# SL_Config_2E.net
KiCad netlist of a schematic drawn in Altium Designer
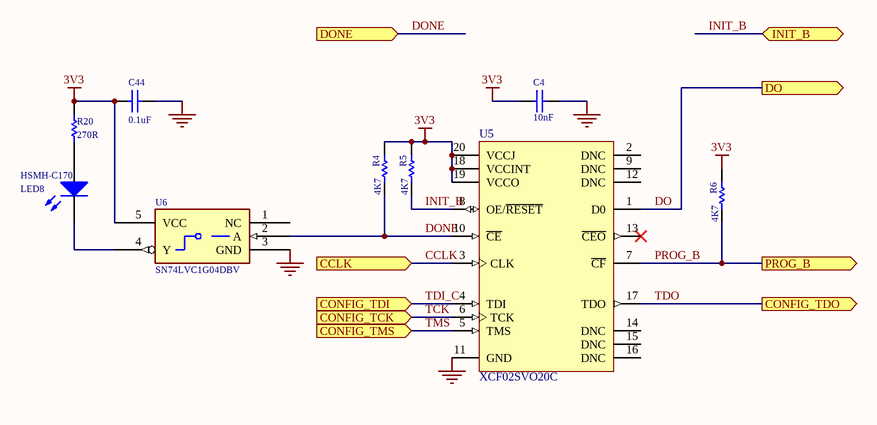
[diagram p0: SL_Config_2E.SchDoc]

(export (version "E")
  (design (tool "Eeschema 10.0.6"))
  (components
    (comp (ref "C4")
      (value "10nF")
      (footprint "CC1608-0603")
      (description "Capacitor")
      (libsource (lib "SpiritLevel_2E") (part "CAP"))
    )
    (comp (ref "C44")
      (value "0.1uF")
      (footprint "CC2012-0805")
      (description "Capacitor")
      (libsource (lib "SpiritLevel_2E") (part "CAP"))
    )
    (comp (ref "LED8")
      (value "HSMH-C170")
      (footprint "Spirit_Level_Project:SMD _LED")
      (description "Typical RED GaAs SMD LED Agilent make")
      (libsource (lib "SpiritLevel_2E") (part "HSMX-C670"))
    )
    (comp (ref "R4")
      (value "4K7")
      (footprint "Spirit_Level_Project:CR2012-0805")
      (description "Resistor")
      (libsource (lib "SpiritLevel_2E") (part "RES"))
    )
    (comp (ref "R5")
      (value "4K7")
      (footprint "Spirit_Level_Project:CR2012-0805")
      (description "Resistor")
      (libsource (lib "SpiritLevel_2E") (part "RES"))
    )
    (comp (ref "R6")
      (value "4K7")
      (footprint "Spirit_Level_Project:CR2012-0805")
      (description "Resistor")
      (libsource (lib "SpiritLevel_2E") (part "RES"))
    )
    (comp (ref "R20")
      (value "270R")
      (footprint "Spirit_Level_Project:CR2012-0805")
      (description "Resistor")
      (libsource (lib "SpiritLevel_2E") (part "RES"))
    )
    (comp (ref "U5")
      (value "XCF02SVO20C")
      (footprint "Spirit_Level_Project:VO20")
      (libsource (lib "SpiritLevel_2E") (part "XCF02SVO20C"))
    )
    (comp (ref "U6")
      (value "SN74LVC1G04DBV")
      (footprint "Spirit_Level_Project:SO-G5/P.95")
      (fields (field (name "MANUFACTURER") "TI"))
      (libsource (lib "SpiritLevel_2E") (part "SN74AHC1G04DBVR"))
    )
  )
  (nets
    (net (code "1") (name "/CCLK") (class "Default")
      (node (ref "U5") (pin "3") (pinfunction "CLK_3") (pintype "input"))
    )
    (net (code "2") (name "/DO") (class "Default")
      (node (ref "U5") (pin "1") (pinfunction "D0_1") (pintype "tri_state"))
    )
    (net (code "3") (name "/DONE") (class "Default")
      (node (ref "R4") (pin "2") (pinfunction "2_2") (pintype "passive"))
      (node (ref "U5") (pin "10") (pinfunction "~{CE}_10") (pintype "input"))
      (node (ref "U6") (pin "2") (pinfunction "A_2") (pintype "input"))
    )
    (net (code "4") (name "/INIT_B") (class "Default")
      (node (ref "R5") (pin "2") (pinfunction "2_2") (pintype "passive"))
      (node (ref "U5") (pin "8") (pinfunction "OE/~{RESET}_8") (pintype "bidirectional"))
    )
    (net (code "5") (name "/PROG_B") (class "Default")
      (node (ref "R6") (pin "2") (pinfunction "2_2") (pintype "passive"))
      (node (ref "U5") (pin "7") (pinfunction "~{CF}_7") (pintype "open_collector"))
    )
    (net (code "6") (name "/TCK") (class "Default")
      (node (ref "U5") (pin "6") (pinfunction "TCK_6") (pintype "input"))
    )
    (net (code "7") (name "/TDI_C") (class "Default")
      (node (ref "U5") (pin "4") (pinfunction "TDI_4") (pintype "input"))
    )
    (net (code "8") (name "/TDO") (class "Default")
      (node (ref "U5") (pin "17") (pinfunction "TDO_17") (pintype "output"))
    )
    (net (code "9") (name "/TMS") (class "Default")
      (node (ref "U5") (pin "5") (pinfunction "TMS_5") (pintype "input"))
    )
    (net (code "10") (name "3V3") (class "Default")
      (node (ref "C4") (pin "1") (pinfunction "1_1") (pintype "passive"))
      (node (ref "C44") (pin "2") (pinfunction "2_2") (pintype "passive"))
      (node (ref "R20") (pin "2") (pinfunction "2_2") (pintype "passive"))
      (node (ref "R4") (pin "1") (pinfunction "1_1") (pintype "passive"))
      (node (ref "R5") (pin "1") (pinfunction "1_1") (pintype "passive"))
      (node (ref "R6") (pin "1") (pinfunction "1_1") (pintype "passive"))
      (node (ref "U5") (pin "18") (pinfunction "VCCINT_18") (pintype "power_in"))
      (node (ref "U5") (pin "19") (pinfunction "VCCO_19") (pintype "power_in"))
      (node (ref "U5") (pin "20") (pinfunction "VCCJ_20") (pintype "power_in"))
      (node (ref "U6") (pin "5") (pinfunction "VCC_5") (pintype "power_in"))
    )
    (net (code "11") (name "GND") (class "Default")
      (node (ref "C4") (pin "2") (pinfunction "2_2") (pintype "passive"))
      (node (ref "C44") (pin "1") (pinfunction "1_1") (pintype "passive"))
      (node (ref "U5") (pin "11") (pinfunction "GND_11") (pintype "power_in"))
      (node (ref "U6") (pin "3") (pinfunction "GND_3") (pintype "power_in"))
    )
    (net (code "12") (name "Net-(LED8-A)") (class "Default")
      (node (ref "LED8") (pin "1") (pinfunction "A_1") (pintype "passive"))
      (node (ref "R20") (pin "1") (pinfunction "1_1") (pintype "passive"))
    )
    (net (code "13") (name "Net-(LED8-K)") (class "Default")
      (node (ref "LED8") (pin "2") (pinfunction "K_2") (pintype "passive"))
      (node (ref "U6") (pin "4") (pinfunction "Y_4") (pintype "output"))
    )
    (net (code "14") (name "unconnected-(U5-DNC-Pad2)") (class "Default")
      (node (ref "U5") (pin "2") (pinfunction "DNC_2") (pintype "passive"))
    )
    (net (code "15") (name "unconnected-(U5-DNC-Pad9)") (class "Default")
      (node (ref "U5") (pin "9") (pinfunction "DNC_9") (pintype "passive"))
    )
    (net (code "16") (name "unconnected-(U5-DNC-Pad12)") (class "Default")
      (node (ref "U5") (pin "12") (pinfunction "DNC_12") (pintype "passive"))
    )
    (net (code "17") (name "unconnected-(U5-DNC-Pad14)") (class "Default")
      (node (ref "U5") (pin "14") (pinfunction "DNC_14") (pintype "passive"))
    )
    (net (code "18") (name "unconnected-(U5-DNC-Pad15)") (class "Default")
      (node (ref "U5") (pin "15") (pinfunction "DNC_15") (pintype "passive"))
    )
    (net (code "19") (name "unconnected-(U5-DNC-Pad16)") (class "Default")
      (node (ref "U5") (pin "16") (pinfunction "DNC_16") (pintype "passive"))
    )
    (net (code "20") (name "unconnected-(U5-~{CEO}-Pad13)") (class "Default")
      (node (ref "U5") (pin "13") (pinfunction "~{CEO}_13") (pintype "output+no_connect"))
    )
    (net (code "21") (name "unconnected-(U6-NC-Pad1)") (class "Default")
      (node (ref "U6") (pin "1") (pinfunction "NC_1") (pintype "passive"))
    )
  )
)
